# 2003.net
KiCad netlist of a schematic drawn in Altium Designer
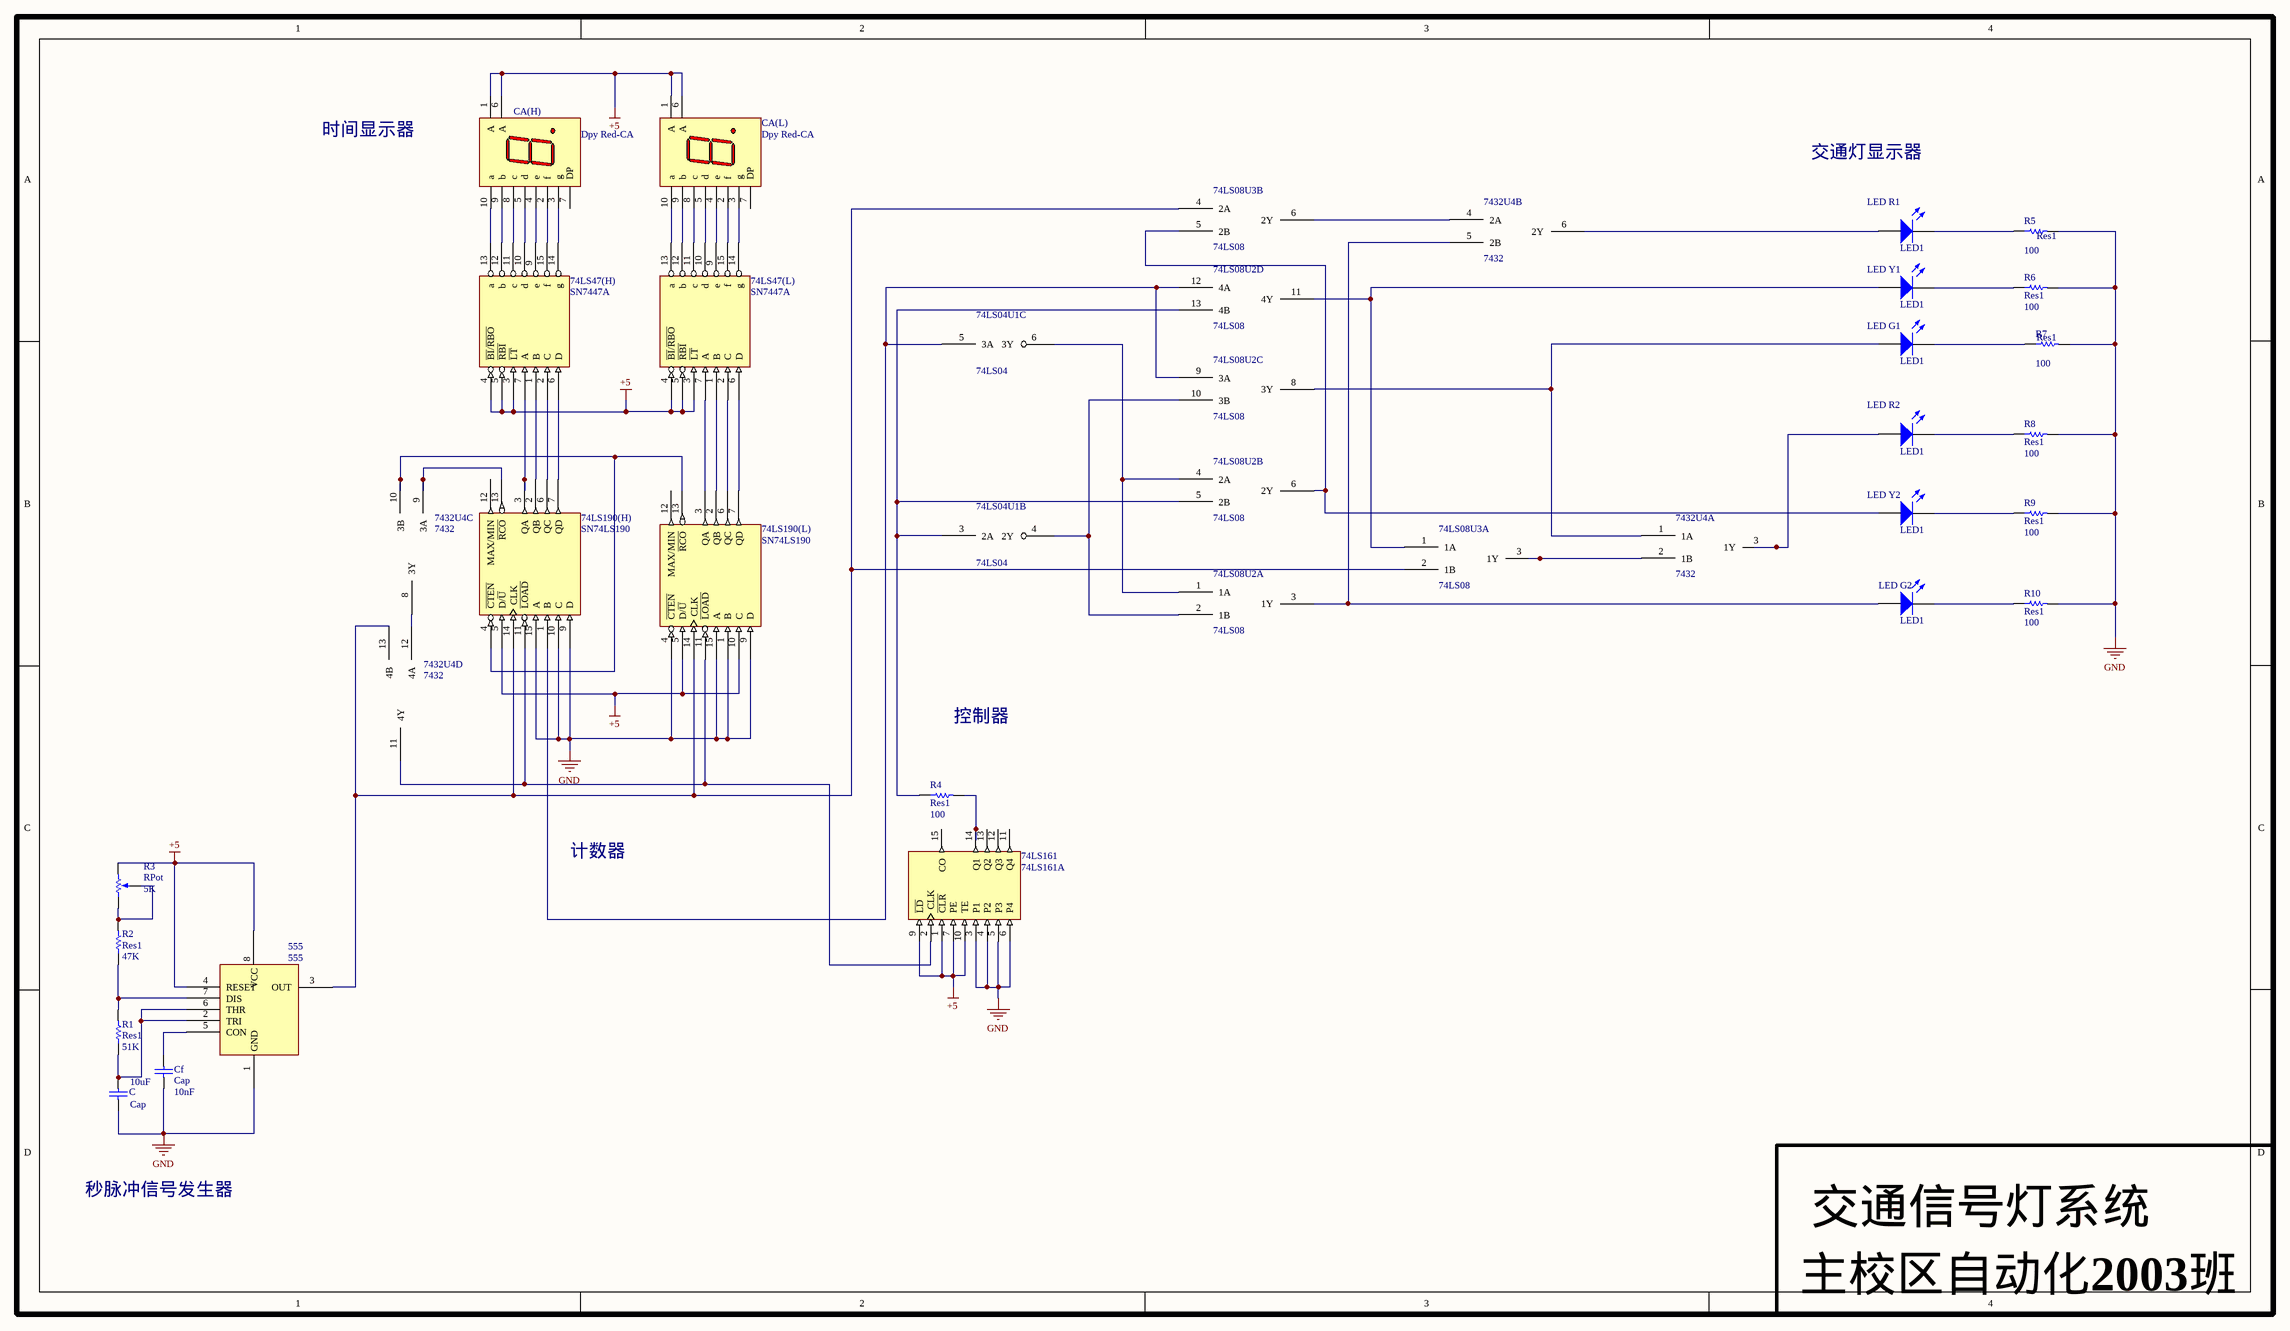
[diagram p0: 本部自动化2003交通信号灯设计.schdoc]

(export (version "E")
  (design (tool "Eeschema 10.0.6"))
  (components
    (comp (ref "74LS04U1") (value "74LS04") (footprint "DIP14") (libsource (lib "shudian") (part "74LS04")))
    (comp (ref "74LS08U2") (value "74LS08") (footprint "DIP14") (libsource (lib "shudian") (part "74LS08")))
    (comp (ref "74LS08U3") (value "74LS08") (footprint "DIP14") (libsource (lib "shudian") (part "74LS08")))
    (comp (ref "74LS47(H)")
      (value "SN7447A")
      (footprint "DIP16")
      (description "BCD-To-SEVEN-SEGMENT DEC DRV")
      (libsource (lib "1.4 - 74系列TTL芯片") (part "SN7446A"))
    )
    (comp (ref "74LS47(L)")
      (value "SN7447A")
      (footprint "DIP-16")
      (description "BCD-To-SEVEN-SEGMENT DEC DRV")
      (libsource (lib "1.4 - 74系列TTL芯片") (part "SN7446A"))
    )
    (comp (ref "74LS161")
      (value "74LS161A")
      (footprint "DIP-16")
      (description "Synchronous 4-Bit Binary Counter with Direct Clear")
      (libsource (lib "1.4 - 74系列TTL芯片") (part "74LS161A"))
    )
    (comp (ref "74LS190(H)")
      (value "SN74LS190")
      (footprint "DIP-16")
      (description "SYN UP/DOWN CNT DOWN/UP MODE CONTTOL")
      (libsource (lib "1.4 - 74系列TTL芯片") (part "SN74LS190"))
    )
    (comp (ref "74LS190(L)")
      (value "SN74LS190")
      (footprint "DIP-16")
      (description "SYN UP/DOWN CNT DOWN/UP MODE CONTTOL")
      (libsource (lib "1.4 - 74系列TTL芯片") (part "SN74LS190"))
    )
    (comp (ref "555") (value "555") (footprint "DIP8") (libsource (lib "Schlib1") (part "555")))
    (comp (ref "7432U4") (value "7432") (footprint "DIP14") (libsource (lib "shudian") (part "7432")))
    (comp (ref "C")
      (value "Cap")
      (footprint "RAD-0.3")
      (description "Capacitor")
      (fields (field (name "ALTIUM_VALUE") "10uF") (field (name "PUBLISHER") "Altium Limited"))
      (libsource (lib "Miscellaneous Devices") (part "Cap"))
    )
    (comp (ref "CA(H)")
      (value "Dpy Red-CA")
      (footprint "A")
      (description "7.62 mm Black Surface HER 7-Segment Display: CA, RH DP")
      (fields (field (name "PUBLISHER") "Altium Limited"))
      (libsource (lib "Miscellaneous Devices") (part "Dpy Red-CA"))
    )
    (comp (ref "CA(L)")
      (value "Dpy Red-CA")
      (footprint "A")
      (description "7.62 mm Black Surface HER 7-Segment Display: CA, RH DP")
      (fields (field (name "PUBLISHER") "Altium Limited"))
      (libsource (lib "Miscellaneous Devices") (part "Dpy Red-CA"))
    )
    (comp (ref "Cf")
      (value "Cap")
      (footprint "RAD-0.3")
      (description "Capacitor")
      (fields (field (name "ALTIUM_VALUE") "10nF") (field (name "PUBLISHER") "Altium Limited"))
      (libsource (lib "Miscellaneous Devices") (part "Cap"))
    )
    (comp (ref "LED G1")
      (value "LED1")
      (footprint "LED-1")
      (description "Typical RED GaAs LED")
      (fields (field (name "PUBLISHER") "Altium Limited"))
      (libsource (lib "Miscellaneous Devices") (part "LED1"))
    )
    (comp (ref "LED G2")
      (value "LED1")
      (footprint "LED-1")
      (description "Typical RED GaAs LED")
      (fields (field (name "PUBLISHER") "Altium Limited"))
      (libsource (lib "Miscellaneous Devices") (part "LED1"))
    )
    (comp (ref "LED R1")
      (value "LED1")
      (footprint "LED-1")
      (description "Typical RED GaAs LED")
      (fields (field (name "PUBLISHER") "Altium Limited"))
      (libsource (lib "Miscellaneous Devices") (part "LED1"))
    )
    (comp (ref "LED R2")
      (value "LED1")
      (footprint "LED-1")
      (description "Typical RED GaAs LED")
      (fields (field (name "PUBLISHER") "Altium Limited"))
      (libsource (lib "Miscellaneous Devices") (part "LED1"))
    )
    (comp (ref "LED Y1")
      (value "LED1")
      (footprint "LED-1")
      (description "Typical RED GaAs LED")
      (fields (field (name "PUBLISHER") "Altium Limited"))
      (libsource (lib "Miscellaneous Devices") (part "LED1"))
    )
    (comp (ref "LED Y2")
      (value "LED1")
      (footprint "LED-1")
      (description "Typical RED GaAs LED")
      (fields (field (name "PUBLISHER") "Altium Limited"))
      (libsource (lib "Miscellaneous Devices") (part "LED1"))
    )
    (comp (ref "R1")
      (value "Res1")
      (footprint "AXIAL-0.3")
      (description "Resistor")
      (fields (field (name "ALTIUM_VALUE") "51K") (field (name "PUBLISHER") "Altium Limited"))
      (libsource (lib "Miscellaneous Devices") (part "Res1"))
    )
    (comp (ref "R2")
      (value "Res1")
      (footprint "AXIAL-0.3")
      (description "Resistor")
      (fields (field (name "ALTIUM_VALUE") "47K") (field (name "PUBLISHER") "Altium Limited"))
      (libsource (lib "Miscellaneous Devices") (part "Res1"))
    )
    (comp (ref "R3")
      (value "RPot")
      (footprint "VR5")
      (description "Potentiometer")
      (fields (field (name "ALTIUM_VALUE") "5K") (field (name "PUBLISHER") "Altium Limited"))
      (libsource (lib "Miscellaneous Devices") (part "RPot"))
    )
    (comp (ref "R4")
      (value "Res1")
      (footprint "AXIAL-0.3")
      (description "Resistor")
      (fields (field (name "ALTIUM_VALUE") "100") (field (name "PUBLISHER") "Altium Limited"))
      (libsource (lib "Miscellaneous Devices") (part "Res1"))
    )
    (comp (ref "R5")
      (value "Res1")
      (footprint "AXIAL-0.3")
      (description "Resistor")
      (fields (field (name "ALTIUM_VALUE") "100") (field (name "PUBLISHER") "Altium Limited"))
      (libsource (lib "Miscellaneous Devices") (part "Res1"))
    )
    (comp (ref "R6")
      (value "Res1")
      (footprint "AXIAL-0.3")
      (description "Resistor")
      (fields (field (name "ALTIUM_VALUE") "100") (field (name "PUBLISHER") "Altium Limited"))
      (libsource (lib "Miscellaneous Devices") (part "Res1"))
    )
    (comp (ref "R7")
      (value "Res1")
      (footprint "AXIAL-0.3")
      (description "Resistor")
      (fields (field (name "ALTIUM_VALUE") "100") (field (name "PUBLISHER") "Altium Limited"))
      (libsource (lib "Miscellaneous Devices") (part "Res1"))
    )
    (comp (ref "R8")
      (value "Res1")
      (footprint "AXIAL-0.3")
      (description "Resistor")
      (fields (field (name "ALTIUM_VALUE") "100") (field (name "PUBLISHER") "Altium Limited"))
      (libsource (lib "Miscellaneous Devices") (part "Res1"))
    )
    (comp (ref "R9")
      (value "Res1")
      (footprint "AXIAL-0.3")
      (description "Resistor")
      (fields (field (name "ALTIUM_VALUE") "100") (field (name "PUBLISHER") "Altium Limited"))
      (libsource (lib "Miscellaneous Devices") (part "Res1"))
    )
    (comp (ref "R10")
      (value "Res1")
      (footprint "AXIAL-0.3")
      (description "Resistor")
      (fields (field (name "ALTIUM_VALUE") "100") (field (name "PUBLISHER") "Altium Limited"))
      (libsource (lib "Miscellaneous Devices") (part "Res1"))
    )
  )
  (nets
    (net (code "1") (name "+5") (class "Default")
      (node (ref "555") (pin "4") (pinfunction "RESET_4") (pintype "passive"))
      (node (ref "555") (pin "8") (pinfunction "VCC_8") (pintype "passive"))
      (node (ref "74LS161") (pin "1") (pinfunction "~{CLR}_1") (pintype "input"))
      (node (ref "74LS161") (pin "10") (pinfunction "TE_10") (pintype "input"))
      (node (ref "74LS161") (pin "7") (pinfunction "PE_7") (pintype "input"))
      (node (ref "74LS161") (pin "9") (pinfunction "~{LD}_9") (pintype "input"))
      (node (ref "74LS190(H)") (pin "5") (pinfunction "D/~{U}_5") (pintype "input"))
      (node (ref "74LS190(L)") (pin "10") (pinfunction "C_10") (pintype "input"))
      (node (ref "74LS190(L)") (pin "5") (pinfunction "D/~{U}_5") (pintype "input"))
      (node (ref "74LS47(H)") (pin "3") (pinfunction "~{LT}_3") (pintype "input"))
      (node (ref "74LS47(H)") (pin "4") (pinfunction "~{BI}/~{RBO}_4") (pintype "input"))
      (node (ref "74LS47(H)") (pin "5") (pinfunction "~{RBI}_5") (pintype "input"))
      (node (ref "74LS47(L)") (pin "3") (pinfunction "~{LT}_3") (pintype "input"))
      (node (ref "74LS47(L)") (pin "4") (pinfunction "~{BI}/~{RBO}_4") (pintype "input"))
      (node (ref "74LS47(L)") (pin "5") (pinfunction "~{RBI}_5") (pintype "input"))
      (node (ref "CA(H)") (pin "1") (pinfunction "A_1") (pintype "passive"))
      (node (ref "CA(H)") (pin "6") (pinfunction "A_6") (pintype "passive"))
      (node (ref "CA(L)") (pin "1") (pinfunction "A_1") (pintype "passive"))
      (node (ref "CA(L)") (pin "6") (pinfunction "A_6") (pintype "passive"))
      (node (ref "R3") (pin "2") (pinfunction "BOT_2") (pintype "passive"))
    )
    (net (code "2") (name "GND") (class "Default")
      (node (ref "555") (pin "1") (pinfunction "GND_1") (pintype "passive"))
      (node (ref "74LS161") (pin "3") (pinfunction "P1_3") (pintype "input"))
      (node (ref "74LS161") (pin "4") (pinfunction "P2_4") (pintype "input"))
      (node (ref "74LS161") (pin "5") (pinfunction "P3_5") (pintype "input"))
      (node (ref "74LS161") (pin "6") (pinfunction "P4_6") (pintype "input"))
      (node (ref "74LS161") (pin "8") (pinfunction "GND_8") (pintype "power_in"))
      (node (ref "74LS190(H)") (pin "10") (pinfunction "C_10") (pintype "input"))
      (node (ref "74LS190(H)") (pin "15") (pinfunction "A_15") (pintype "input"))
      (node (ref "74LS190(H)") (pin "8") (pinfunction "GND_8") (pintype "power_in"))
      (node (ref "74LS190(H)") (pin "9") (pinfunction "D_9") (pintype "input"))
      (node (ref "74LS190(L)") (pin "1") (pinfunction "B_1") (pintype "input"))
      (node (ref "74LS190(L)") (pin "15") (pinfunction "A_15") (pintype "input"))
      (node (ref "74LS190(L)") (pin "4") (pinfunction "~{CTEN}_4") (pintype "input"))
      (node (ref "74LS190(L)") (pin "8") (pinfunction "GND_8") (pintype "power_in"))
      (node (ref "74LS190(L)") (pin "9") (pinfunction "D_9") (pintype "input"))
      (node (ref "74LS47(H)") (pin "8") (pinfunction "GND_8") (pintype "power_in"))
      (node (ref "74LS47(L)") (pin "8") (pinfunction "GND_8") (pintype "power_in"))
      (node (ref "C") (pin "1") (pinfunction "1_1") (pintype "passive"))
      (node (ref "Cf") (pin "1") (pinfunction "1_1") (pintype "passive"))
      (node (ref "R10") (pin "2") (pinfunction "2_2") (pintype "passive"))
      (node (ref "R5") (pin "2") (pinfunction "2_2") (pintype "passive"))
      (node (ref "R6") (pin "2") (pinfunction "2_2") (pintype "passive"))
      (node (ref "R7") (pin "2") (pinfunction "2_2") (pintype "passive"))
      (node (ref "R8") (pin "2") (pinfunction "2_2") (pintype "passive"))
      (node (ref "R9") (pin "2") (pinfunction "2_2") (pintype "passive"))
    )
    (net (code "3") (name "Net-(74LS04U1B-2A)") (class "Default")
      (node (ref "74LS04U1") (pin "3") (pinfunction "2A_3") (pintype "passive"))
      (node (ref "74LS08U2") (pin "13") (pinfunction "4B_13") (pintype "passive"))
      (node (ref "74LS08U2") (pin "5") (pinfunction "2B_5") (pintype "passive"))
      (node (ref "R4") (pin "1") (pinfunction "1_1") (pintype "passive"))
    )
    (net (code "4") (name "Net-(74LS04U1B-2Y)") (class "Default")
      (node (ref "74LS04U1") (pin "4") (pinfunction "2Y_4") (pintype "passive"))
      (node (ref "74LS08U2") (pin "10") (pinfunction "3B_10") (pintype "passive"))
      (node (ref "74LS08U2") (pin "2") (pinfunction "1B_2") (pintype "passive"))
    )
    (net (code "5") (name "Net-(74LS04U1C-3A)") (class "Default")
      (node (ref "74LS04U1") (pin "5") (pinfunction "3A_5") (pintype "passive"))
      (node (ref "74LS08U2") (pin "12") (pinfunction "4A_12") (pintype "passive"))
      (node (ref "74LS08U2") (pin "9") (pinfunction "3A_9") (pintype "passive"))
      (node (ref "74LS190(H)") (pin "1") (pinfunction "B_1") (pintype "input"))
    )
    (net (code "6") (name "Net-(74LS04U1C-3Y)") (class "Default")
      (node (ref "74LS04U1") (pin "6") (pinfunction "3Y_6") (pintype "passive"))
      (node (ref "74LS08U2") (pin "1") (pinfunction "1A_1") (pintype "passive"))
      (node (ref "74LS08U2") (pin "4") (pinfunction "2A_4") (pintype "passive"))
    )
    (net (code "7") (name "Net-(74LS08U2B-2Y)") (class "Default")
      (node (ref "74LS08U2") (pin "6") (pinfunction "2Y_6") (pintype "passive"))
      (node (ref "74LS08U3") (pin "5") (pinfunction "2B_5") (pintype "passive"))
      (node (ref "LED Y2") (pin "1") (pinfunction "A_1") (pintype "passive"))
    )
    (net (code "8") (name "Net-(74LS08U2D-4Y)") (class "Default")
      (node (ref "74LS08U2") (pin "11") (pinfunction "4Y_11") (pintype "passive"))
      (node (ref "74LS08U3") (pin "1") (pinfunction "1A_1") (pintype "passive"))
      (node (ref "LED Y1") (pin "1") (pinfunction "A_1") (pintype "passive"))
    )
    (net (code "9") (name "Net-(74LS47(H)-a)") (class "Default")
      (node (ref "74LS47(H)") (pin "13") (pinfunction "a_13") (pintype "open_collector"))
      (node (ref "CA(H)") (pin "10") (pinfunction "a_10") (pintype "passive"))
    )
    (net (code "10") (name "Net-(74LS47(H)-b)") (class "Default")
      (node (ref "74LS47(H)") (pin "12") (pinfunction "b_12") (pintype "open_collector"))
      (node (ref "CA(H)") (pin "9") (pinfunction "b_9") (pintype "passive"))
    )
    (net (code "11") (name "Net-(74LS47(H)-c)") (class "Default")
      (node (ref "74LS47(H)") (pin "11") (pinfunction "c_11") (pintype "open_collector"))
      (node (ref "CA(H)") (pin "8") (pinfunction "c_8") (pintype "passive"))
    )
    (net (code "12") (name "Net-(74LS47(H)-d)") (class "Default")
      (node (ref "74LS47(H)") (pin "10") (pinfunction "d_10") (pintype "open_collector"))
      (node (ref "CA(H)") (pin "5") (pinfunction "d_5") (pintype "passive"))
    )
    (net (code "13") (name "Net-(74LS47(H)-e)") (class "Default")
      (node (ref "74LS47(H)") (pin "9") (pinfunction "e_9") (pintype "open_collector"))
      (node (ref "CA(H)") (pin "4") (pinfunction "e_4") (pintype "passive"))
    )
    (net (code "14") (name "Net-(74LS47(H)-f)") (class "Default")
      (node (ref "74LS47(H)") (pin "15") (pinfunction "f_15") (pintype "open_collector"))
      (node (ref "CA(H)") (pin "2") (pinfunction "f_2") (pintype "passive"))
    )
    (net (code "15") (name "Net-(74LS47(H)-g)") (class "Default")
      (node (ref "74LS47(H)") (pin "14") (pinfunction "g_14") (pintype "open_collector"))
      (node (ref "CA(H)") (pin "3") (pinfunction "g_3") (pintype "passive"))
    )
    (net (code "16") (name "Net-(74LS47(L)-a)") (class "Default")
      (node (ref "74LS47(L)") (pin "13") (pinfunction "a_13") (pintype "open_collector"))
      (node (ref "CA(L)") (pin "10") (pinfunction "a_10") (pintype "passive"))
    )
    (net (code "17") (name "Net-(74LS47(L)-b)") (class "Default")
      (node (ref "74LS47(L)") (pin "12") (pinfunction "b_12") (pintype "open_collector"))
      (node (ref "CA(L)") (pin "9") (pinfunction "b_9") (pintype "passive"))
    )
    (net (code "18") (name "Net-(74LS47(L)-c)") (class "Default")
      (node (ref "74LS47(L)") (pin "11") (pinfunction "c_11") (pintype "open_collector"))
      (node (ref "CA(L)") (pin "8") (pinfunction "c_8") (pintype "passive"))
    )
    (net (code "19") (name "Net-(74LS47(L)-d)") (class "Default")
      (node (ref "74LS47(L)") (pin "10") (pinfunction "d_10") (pintype "open_collector"))
      (node (ref "CA(L)") (pin "5") (pinfunction "d_5") (pintype "passive"))
    )
    (net (code "20") (name "Net-(74LS47(L)-e)") (class "Default")
      (node (ref "74LS47(L)") (pin "9") (pinfunction "e_9") (pintype "open_collector"))
      (node (ref "CA(L)") (pin "4") (pinfunction "e_4") (pintype "passive"))
    )
    (net (code "21") (name "Net-(74LS47(L)-f)") (class "Default")
      (node (ref "74LS47(L)") (pin "15") (pinfunction "f_15") (pintype "open_collector"))
      (node (ref "CA(L)") (pin "2") (pinfunction "f_2") (pintype "passive"))
    )
    (net (code "22") (name "Net-(74LS47(L)-g)") (class "Default")
      (node (ref "74LS47(L)") (pin "14") (pinfunction "g_14") (pintype "open_collector"))
      (node (ref "CA(L)") (pin "3") (pinfunction "g_3") (pintype "passive"))
    )
    (net (code "23") (name "Net-(74LS161-Q1)") (class "Default")
      (node (ref "74LS161") (pin "14") (pinfunction "Q1_14") (pintype "output"))
      (node (ref "R4") (pin "2") (pinfunction "2_2") (pintype "passive"))
    )
    (net (code "24") (name "Net-(74LS190(H)-QA)") (class "Default")
      (node (ref "74LS190(H)") (pin "3") (pinfunction "QA_3") (pintype "output"))
      (node (ref "74LS47(H)") (pin "7") (pinfunction "A_7") (pintype "input"))
    )
    (net (code "25") (name "Net-(74LS190(H)-QB)") (class "Default")
      (node (ref "74LS190(H)") (pin "2") (pinfunction "QB_2") (pintype "output"))
      (node (ref "74LS47(H)") (pin "1") (pinfunction "B_1") (pintype "input"))
    )
    (net (code "26") (name "Net-(74LS190(H)-QC)") (class "Default")
      (node (ref "74LS190(H)") (pin "6") (pinfunction "QC_6") (pintype "output"))
      (node (ref "74LS47(H)") (pin "2") (pinfunction "C_2") (pintype "input"))
    )
    (net (code "27") (name "Net-(74LS190(H)-QD)") (class "Default")
      (node (ref "74LS190(H)") (pin "7") (pinfunction "QD_7") (pintype "output"))
      (node (ref "74LS47(H)") (pin "6") (pinfunction "D_6") (pintype "input"))
    )
    (net (code "28") (name "Net-(74LS190(L)-QA)") (class "Default")
      (node (ref "74LS190(L)") (pin "3") (pinfunction "QA_3") (pintype "output"))
      (node (ref "74LS47(L)") (pin "7") (pinfunction "A_7") (pintype "input"))
    )
    (net (code "29") (name "Net-(74LS190(L)-QB)") (class "Default")
      (node (ref "74LS190(L)") (pin "2") (pinfunction "QB_2") (pintype "output"))
      (node (ref "74LS47(L)") (pin "1") (pinfunction "B_1") (pintype "input"))
    )
    (net (code "30") (name "Net-(74LS190(L)-QC)") (class "Default")
      (node (ref "74LS190(L)") (pin "6") (pinfunction "QC_6") (pintype "output"))
      (node (ref "74LS47(L)") (pin "2") (pinfunction "C_2") (pintype "input"))
    )
    (net (code "31") (name "Net-(74LS190(L)-QD)") (class "Default")
      (node (ref "74LS190(L)") (pin "7") (pinfunction "QD_7") (pintype "output"))
      (node (ref "74LS47(L)") (pin "6") (pinfunction "D_6") (pintype "input"))
    )
    (net (code "32") (name "Net-(555-CON)") (class "Default")
      (node (ref "555") (pin "5") (pinfunction "CON_5") (pintype "passive"))
      (node (ref "Cf") (pin "2") (pinfunction "2_2") (pintype "passive"))
    )
    (net (code "33") (name "Net-(555-DIS)") (class "Default")
      (node (ref "555") (pin "7") (pinfunction "DIS_7") (pintype "passive"))
      (node (ref "R1") (pin "2") (pinfunction "2_2") (pintype "passive"))
      (node (ref "R2") (pin "1") (pinfunction "1_1") (pintype "passive"))
    )
    (net (code "34") (name "Net-(555-OUT)") (class "Default")
      (node (ref "555") (pin "3") (pinfunction "OUT_3") (pintype "passive"))
      (node (ref "7432U4") (pin "13") (pinfunction "4B_13") (pintype "passive"))
      (node (ref "74LS08U3") (pin "2") (pinfunction "1B_2") (pintype "passive"))
      (node (ref "74LS08U3") (pin "4") (pinfunction "2A_4") (pintype "passive"))
      (node (ref "74LS190(H)") (pin "14") (pinfunction "CLK_14") (pintype "input"))
      (node (ref "74LS190(L)") (pin "14") (pinfunction "CLK_14") (pintype "input"))
    )
    (net (code "35") (name "Net-(555-THR)") (class "Default")
      (node (ref "555") (pin "2") (pinfunction "TRI_2") (pintype "passive"))
      (node (ref "555") (pin "6") (pinfunction "THR_6") (pintype "passive"))
      (node (ref "C") (pin "2") (pinfunction "2_2") (pintype "passive"))
      (node (ref "R1") (pin "1") (pinfunction "1_1") (pintype "passive"))
    )
    (net (code "36") (name "Net-(7432U4A-1A)") (class "Default")
      (node (ref "7432U4") (pin "1") (pinfunction "1A_1") (pintype "passive"))
      (node (ref "74LS08U2") (pin "8") (pinfunction "3Y_8") (pintype "passive"))
      (node (ref "LED G1") (pin "1") (pinfunction "A_1") (pintype "passive"))
    )
    (net (code "37") (name "Net-(7432U4A-1B)") (class "Default")
      (node (ref "7432U4") (pin "2") (pinfunction "1B_2") (pintype "passive"))
      (node (ref "74LS08U3") (pin "3") (pinfunction "1Y_3") (pintype "passive"))
    )
    (net (code "38") (name "Net-(7432U4A-1Y)") (class "Default")
      (node (ref "7432U4") (pin "3") (pinfunction "1Y_3") (pintype "passive"))
      (node (ref "LED R2") (pin "1") (pinfunction "A_1") (pintype "passive"))
    )
    (net (code "39") (name "Net-(7432U4B-2A)") (class "Default")
      (node (ref "7432U4") (pin "4") (pinfunction "2A_4") (pintype "passive"))
      (node (ref "74LS08U3") (pin "6") (pinfunction "2Y_6") (pintype "passive"))
    )
    (net (code "40") (name "Net-(7432U4B-2B)") (class "Default")
      (node (ref "7432U4") (pin "5") (pinfunction "2B_5") (pintype "passive"))
      (node (ref "74LS08U2") (pin "3") (pinfunction "1Y_3") (pintype "passive"))
      (node (ref "LED G2") (pin "1") (pinfunction "A_1") (pintype "passive"))
    )
    (net (code "41") (name "Net-(7432U4B-2Y)") (class "Default")
      (node (ref "7432U4") (pin "6") (pinfunction "2Y_6") (pintype "passive"))
      (node (ref "LED R1") (pin "1") (pinfunction "A_1") (pintype "passive"))
    )
    (net (code "42") (name "Net-(7432U4C-3A)") (class "Default")
      (node (ref "7432U4") (pin "9") (pinfunction "3A_9") (pintype "passive"))
      (node (ref "74LS190(H)") (pin "13") (pinfunction "~{RCO}_13") (pintype "output"))
    )
    (net (code "43") (name "Net-(7432U4C-3B)") (class "Default")
      (node (ref "7432U4") (pin "10") (pinfunction "3B_10") (pintype "passive"))
      (node (ref "74LS190(H)") (pin "4") (pinfunction "~{CTEN}_4") (pintype "input"))
      (node (ref "74LS190(L)") (pin "13") (pinfunction "~{RCO}_13") (pintype "output"))
    )
    (net (code "44") (name "Net-(7432U4C-3Y)") (class "Default")
      (node (ref "7432U4") (pin "12") (pinfunction "4A_12") (pintype "passive"))
      (node (ref "7432U4") (pin "8") (pinfunction "3Y_8") (pintype "passive"))
    )
    (net (code "45") (name "Net-(7432U4D-4Y)") (class "Default")
      (node (ref "7432U4") (pin "11") (pinfunction "4Y_11") (pintype "passive"))
      (node (ref "74LS161") (pin "2") (pinfunction "CLK_2") (pintype "input"))
      (node (ref "74LS190(H)") (pin "11") (pinfunction "~{LOAD}_11") (pintype "input"))
      (node (ref "74LS190(L)") (pin "11") (pinfunction "~{LOAD}_11") (pintype "input"))
    )
    (net (code "46") (name "Net-(LED G1-K)") (class "Default")
      (node (ref "LED G1") (pin "2") (pinfunction "K_2") (pintype "passive"))
      (node (ref "R7") (pin "1") (pinfunction "1_1") (pintype "passive"))
    )
    (net (code "47") (name "Net-(LED G2-K)") (class "Default")
      (node (ref "LED G2") (pin "2") (pinfunction "K_2") (pintype "passive"))
      (node (ref "R10") (pin "1") (pinfunction "1_1") (pintype "passive"))
    )
    (net (code "48") (name "Net-(LED R1-K)") (class "Default")
      (node (ref "LED R1") (pin "2") (pinfunction "K_2") (pintype "passive"))
      (node (ref "R5") (pin "1") (pinfunction "1_1") (pintype "passive"))
    )
    (net (code "49") (name "Net-(LED R2-K)") (class "Default")
      (node (ref "LED R2") (pin "2") (pinfunction "K_2") (pintype "passive"))
      (node (ref "R8") (pin "1") (pinfunction "1_1") (pintype "passive"))
    )
    (net (code "50") (name "Net-(LED Y1-K)") (class "Default")
      (node (ref "LED Y1") (pin "2") (pinfunction "K_2") (pintype "passive"))
      (node (ref "R6") (pin "1") (pinfunction "1_1") (pintype "passive"))
    )
    (net (code "51") (name "Net-(LED Y2-K)") (class "Default")
      (node (ref "LED Y2") (pin "2") (pinfunction "K_2") (pintype "passive"))
      (node (ref "R9") (pin "1") (pinfunction "1_1") (pintype "passive"))
    )
    (net (code "52") (name "Net-(R3-TAP)") (class "Default")
      (node (ref "R2") (pin "2") (pinfunction "2_2") (pintype "passive"))
      (node (ref "R3") (pin "1") (pinfunction "TOP_1") (pintype "passive"))
      (node (ref "R3") (pin "3") (pinfunction "TAP_3") (pintype "passive"))
    )
    (net (code "53") (name "VCC") (class "Default")
      (node (ref "74LS161") (pin "16") (pinfunction "VCC_16") (pintype "power_in"))
      (node (ref "74LS190(H)") (pin "16") (pinfunction "VCC_16") (pintype "power_in"))
      (node (ref "74LS190(L)") (pin "16") (pinfunction "VCC_16") (pintype "power_in"))
      (node (ref "74LS47(H)") (pin "16") (pinfunction "VCC_16") (pintype "power_in"))
      (node (ref "74LS47(L)") (pin "16") (pinfunction "VCC_16") (pintype "power_in"))
    )
    (net (code "54") (name "unconnected-(74LS161-CO-Pad15)") (class "Default")
      (node (ref "74LS161") (pin "15") (pinfunction "CO_15") (pintype "output"))
    )
    (net (code "55") (name "unconnected-(74LS161-Q2-Pad13)") (class "Default")
      (node (ref "74LS161") (pin "13") (pinfunction "Q2_13") (pintype "output"))
    )
    (net (code "56") (name "unconnected-(74LS161-Q3-Pad12)") (class "Default")
      (node (ref "74LS161") (pin "12") (pinfunction "Q3_12") (pintype "output"))
    )
    (net (code "57") (name "unconnected-(74LS161-Q4-Pad11)") (class "Default")
      (node (ref "74LS161") (pin "11") (pinfunction "Q4_11") (pintype "output"))
    )
    (net (code "58") (name "unconnected-(74LS190(H)-MAX{slash}MIN-Pad12)") (class "Default")
      (node (ref "74LS190(H)") (pin "12") (pinfunction "MAX/MIN_12") (pintype "output"))
    )
    (net (code "59") (name "unconnected-(74LS190(L)-MAX{slash}MIN-Pad12)") (class "Default")
      (node (ref "74LS190(L)") (pin "12") (pinfunction "MAX/MIN_12") (pintype "output"))
    )
    (net (code "60") (name "unconnected-(CA(H)-DP-Pad7)") (class "Default")
      (node (ref "CA(H)") (pin "7") (pinfunction "DP_7") (pintype "passive"))
    )
    (net (code "61") (name "unconnected-(CA(L)-DP-Pad7)") (class "Default")
      (node (ref "CA(L)") (pin "7") (pinfunction "DP_7") (pintype "passive"))
    )
  )
)
